# 3PCurrentTX.net
KiCad netlist of a schematic drawn in EAGLE
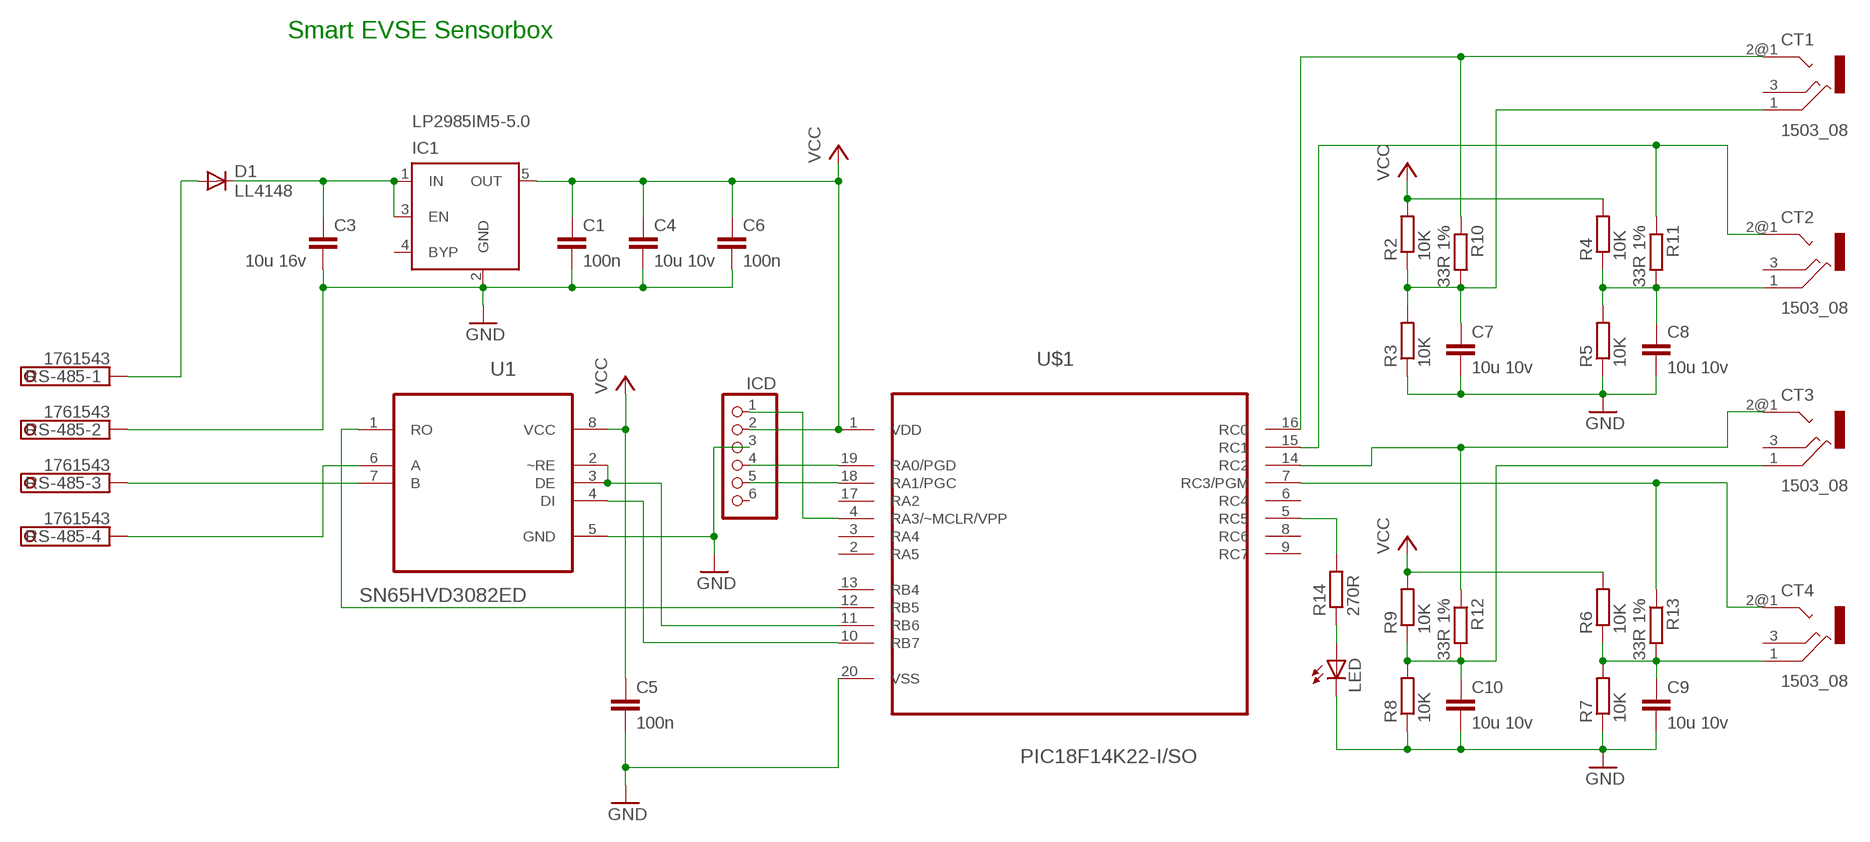
[diagram p0: schematic, sheet 1]

(export (version "E")
  (design (tool "Eeschema 10.0.6"))
  (components
    (comp (ref "C1")
      (value "100n")
      (footprint "eagle-import:C0805K")
      (libsource (lib "eagle-import") (part "C-EUC0805K"))
    )
    (comp (ref "C3")
      (value "10u 16v")
      (footprint "eagle-import:C1206K")
      (libsource (lib "eagle-import") (part "C-EUC1206K"))
    )
    (comp (ref "C4")
      (value "10u 10v")
      (footprint "eagle-import:C0805K")
      (libsource (lib "eagle-import") (part "C-EUC0805K"))
    )
    (comp (ref "C5")
      (value "100n")
      (footprint "eagle-import:C0805K")
      (libsource (lib "eagle-import") (part "C-EUC0805K"))
    )
    (comp (ref "C6")
      (value "100n")
      (footprint "eagle-import:C0805K")
      (libsource (lib "eagle-import") (part "C-EUC0805K"))
    )
    (comp (ref "C7")
      (value "10u 10v")
      (footprint "eagle-import:C0805K")
      (libsource (lib "eagle-import") (part "C-EUC0805K"))
    )
    (comp (ref "C8")
      (value "10u 10v")
      (footprint "eagle-import:C0805K")
      (libsource (lib "eagle-import") (part "C-EUC0805K"))
    )
    (comp (ref "C9")
      (value "10u 10v")
      (footprint "eagle-import:C0805K")
      (libsource (lib "eagle-import") (part "C-EUC0805K"))
    )
    (comp (ref "C10")
      (value "10u 10v")
      (footprint "eagle-import:C0805K")
      (libsource (lib "eagle-import") (part "C-EUC0805K"))
    )
    (comp (ref "CT1")
      (value "1503_08")
      (footprint "eagle-import:1503_08")
      (libsource (lib "eagle-import") (part "1503_?08"))
    )
    (comp (ref "CT2")
      (value "1503_08")
      (footprint "eagle-import:1503_08")
      (libsource (lib "eagle-import") (part "1503_?08"))
    )
    (comp (ref "CT3")
      (value "1503_08")
      (footprint "eagle-import:1503_08")
      (libsource (lib "eagle-import") (part "1503_?08"))
    )
    (comp (ref "CT4")
      (value "1503_08")
      (footprint "eagle-import:1503_08")
      (libsource (lib "eagle-import") (part "1503_?08"))
    )
    (comp (ref "D1")
      (value "LL4148")
      (footprint "eagle-import:SOD123")
      (libsource (lib "eagle-import") (part "DIODE-SOD123"))
    )
    (comp (ref "IC1")
      (value "LP2985IM5-5.0")
      (footprint "eagle-import:SOT23-5")
      (libsource (lib "eagle-import") (part "MIC5219XX"))
    )
    (comp (ref "ICD")
      (value "PINHD-1X6")
      (footprint "eagle-import:1X06")
      (libsource (lib "eagle-import") (part "PINHD-1X6"))
    )
    (comp (ref "LED")
      (value "LEDSML0805")
      (footprint "eagle-import:SML0805")
      (libsource (lib "eagle-import") (part "LEDSML0805"))
    )
    (comp (ref "R2")
      (value "10K")
      (footprint "eagle-import:R0805")
      (libsource (lib "eagle-import") (part "R-EU_R0805"))
    )
    (comp (ref "R3")
      (value "10K")
      (footprint "eagle-import:R0805")
      (libsource (lib "eagle-import") (part "R-EU_R0805"))
    )
    (comp (ref "R4")
      (value "10K")
      (footprint "eagle-import:R0805")
      (libsource (lib "eagle-import") (part "R-EU_R0805"))
    )
    (comp (ref "R5")
      (value "10K")
      (footprint "eagle-import:R0805")
      (libsource (lib "eagle-import") (part "R-EU_R0805"))
    )
    (comp (ref "R6")
      (value "10K")
      (footprint "eagle-import:R0805")
      (libsource (lib "eagle-import") (part "R-EU_R0805"))
    )
    (comp (ref "R7")
      (value "10K")
      (footprint "eagle-import:R0805")
      (libsource (lib "eagle-import") (part "R-EU_R0805"))
    )
    (comp (ref "R8")
      (value "10K")
      (footprint "eagle-import:R0805")
      (libsource (lib "eagle-import") (part "R-EU_R0805"))
    )
    (comp (ref "R9")
      (value "10K")
      (footprint "eagle-import:R0805")
      (libsource (lib "eagle-import") (part "R-EU_R0805"))
    )
    (comp (ref "R10")
      (value "33R 1%")
      (footprint "eagle-import:R0805")
      (libsource (lib "eagle-import") (part "R-EU_R0805"))
    )
    (comp (ref "R11")
      (value "33R 1%")
      (footprint "eagle-import:R0805")
      (libsource (lib "eagle-import") (part "R-EU_R0805"))
    )
    (comp (ref "R12")
      (value "33R 1%")
      (footprint "eagle-import:R0805")
      (libsource (lib "eagle-import") (part "R-EU_R0805"))
    )
    (comp (ref "R13")
      (value "33R 1%")
      (footprint "eagle-import:R0805")
      (libsource (lib "eagle-import") (part "R-EU_R0805"))
    )
    (comp (ref "R14")
      (value "270R")
      (footprint "eagle-import:R0805")
      (libsource (lib "eagle-import") (part "R-EU_R0805"))
    )
    (comp (ref "RS-485")
      (value "1761543")
      (footprint "eagle-import:1751264")
      (fields (field (name "MPN") "1751264"))
      (libsource (lib "eagle-import") (part "1751264"))
    )
    (comp (ref "U$1")
      (value "PIC18F14K22-I/SO")
      (footprint "eagle-import:SOIC127P1030X265-20N")
      (fields (field (name "MPN") "PIC18F14k22-I/SO") (field (name "MPN_1") "PIC18F14k22-I/SO"))
      (libsource (lib "eagle-import") (part "PIC18F14K22-I/SO"))
    )
    (comp (ref "U1")
      (value "SN65HVD3082ED")
      (footprint "eagle-import:SOIC127P600X175-8N")
      (fields (field (name "MPN") "MAX487ECSA+"))
      (libsource (lib "eagle-import") (part "MAX487ECSA+"))
    )
  )
  (nets
    (net (code "1") (name "GND") (class "Default")
      (node (ref "C1") (pin "2") (pinfunction "2_2") (pintype "passive"))
      (node (ref "C10") (pin "2") (pinfunction "2_2") (pintype "passive"))
      (node (ref "C3") (pin "2") (pinfunction "2_2") (pintype "passive"))
      (node (ref "C4") (pin "2") (pinfunction "2_2") (pintype "passive"))
      (node (ref "C5") (pin "2") (pinfunction "2_2") (pintype "passive"))
      (node (ref "C6") (pin "2") (pinfunction "2_2") (pintype "passive"))
      (node (ref "C7") (pin "2") (pinfunction "2_2") (pintype "passive"))
      (node (ref "C8") (pin "2") (pinfunction "2_2") (pintype "passive"))
      (node (ref "C9") (pin "2") (pinfunction "2_2") (pintype "passive"))
      (node (ref "IC1") (pin "2") (pinfunction "GND_2") (pintype "power_in"))
      (node (ref "ICD") (pin "3") (pinfunction "3_3") (pintype "passive"))
      (node (ref "LED") (pin "C") (pinfunction "C_C") (pintype "passive"))
      (node (ref "R3") (pin "1") (pinfunction "1_1") (pintype "passive"))
      (node (ref "R5") (pin "1") (pinfunction "1_1") (pintype "passive"))
      (node (ref "R7") (pin "1") (pinfunction "1_1") (pintype "passive"))
      (node (ref "R8") (pin "1") (pinfunction "1_1") (pintype "passive"))
      (node (ref "RS-485") (pin "2") (pinfunction "K_2") (pintype "passive"))
      (node (ref "U$1") (pin "20") (pinfunction "VSS_20") (pintype "passive"))
      (node (ref "U1") (pin "5") (pinfunction "GND_5") (pintype "passive"))
    )
    (net (code "2") (name "Net-(C7-Pad1)") (class "Default")
      (node (ref "C7") (pin "1") (pinfunction "1_1") (pintype "passive"))
      (node (ref "CT1") (pin "1") (pinfunction "1_1") (pintype "passive"))
      (node (ref "R10") (pin "2") (pinfunction "2_2") (pintype "passive"))
      (node (ref "R2") (pin "1") (pinfunction "1_1") (pintype "passive"))
      (node (ref "R3") (pin "2") (pinfunction "2_2") (pintype "passive"))
    )
    (net (code "3") (name "Net-(C8-Pad1)") (class "Default")
      (node (ref "C8") (pin "1") (pinfunction "1_1") (pintype "passive"))
      (node (ref "CT2") (pin "1") (pinfunction "1_1") (pintype "passive"))
      (node (ref "R11") (pin "2") (pinfunction "2_2") (pintype "passive"))
      (node (ref "R4") (pin "1") (pinfunction "1_1") (pintype "passive"))
      (node (ref "R5") (pin "2") (pinfunction "2_2") (pintype "passive"))
    )
    (net (code "4") (name "Net-(C9-Pad1)") (class "Default")
      (node (ref "C9") (pin "1") (pinfunction "1_1") (pintype "passive"))
      (node (ref "CT4") (pin "1") (pinfunction "1_1") (pintype "passive"))
      (node (ref "R13") (pin "2") (pinfunction "2_2") (pintype "passive"))
      (node (ref "R6") (pin "1") (pinfunction "1_1") (pintype "passive"))
      (node (ref "R7") (pin "2") (pinfunction "2_2") (pintype "passive"))
    )
    (net (code "5") (name "Net-(C10-Pad1)") (class "Default")
      (node (ref "C10") (pin "1") (pinfunction "1_1") (pintype "passive"))
      (node (ref "CT3") (pin "1") (pinfunction "1_1") (pintype "passive"))
      (node (ref "R12") (pin "2") (pinfunction "2_2") (pintype "passive"))
      (node (ref "R8") (pin "2") (pinfunction "2_2") (pintype "passive"))
      (node (ref "R9") (pin "1") (pinfunction "1_1") (pintype "passive"))
    )
    (net (code "6") (name "Net-(IC1-EN)") (class "Default")
      (node (ref "C3") (pin "1") (pinfunction "1_1") (pintype "passive"))
      (node (ref "D1") (pin "C") (pinfunction "C_C") (pintype "passive"))
      (node (ref "IC1") (pin "1") (pinfunction "IN_1") (pintype "input"))
      (node (ref "IC1") (pin "3") (pinfunction "EN_3") (pintype "input"))
    )
    (net (code "7") (name "Net-(LED-PadA)") (class "Default")
      (node (ref "LED") (pin "A") (pinfunction "A_A") (pintype "passive"))
      (node (ref "R14") (pin "1") (pinfunction "1_1") (pintype "passive"))
    )
    (net (code "8") (name "Net-(RS-485A-K)") (class "Default")
      (node (ref "D1") (pin "A") (pinfunction "A_A") (pintype "passive"))
      (node (ref "RS-485") (pin "1") (pinfunction "K_1") (pintype "passive"))
    )
    (net (code "9") (name "Net-(RS-485C-K)") (class "Default")
      (node (ref "RS-485") (pin "3") (pinfunction "K_3") (pintype "passive"))
      (node (ref "U1") (pin "7") (pinfunction "B_7") (pintype "bidirectional"))
    )
    (net (code "10") (name "Net-(RS-485D-K)") (class "Default")
      (node (ref "RS-485") (pin "4") (pinfunction "K_4") (pintype "passive"))
      (node (ref "U1") (pin "6") (pinfunction "A_6") (pintype "bidirectional"))
    )
    (net (code "11") (name "Net-(U$1-RA0{slash}PGD)") (class "Default")
      (node (ref "ICD") (pin "4") (pinfunction "4_4") (pintype "passive"))
      (node (ref "U$1") (pin "19") (pinfunction "RA0/PGD_19") (pintype "bidirectional"))
    )
    (net (code "12") (name "Net-(U$1-RA1{slash}PGC)") (class "Default")
      (node (ref "ICD") (pin "5") (pinfunction "5_5") (pintype "passive"))
      (node (ref "U$1") (pin "18") (pinfunction "RA1/PGC_18") (pintype "bidirectional"))
    )
    (net (code "13") (name "Net-(U$1-RA3{slash}~{MCLR{slash}VPP})") (class "Default")
      (node (ref "ICD") (pin "1") (pinfunction "1_1") (pintype "passive"))
      (node (ref "U$1") (pin "4") (pinfunction "RA3/~{MCLR/VPP}_4") (pintype "bidirectional"))
    )
    (net (code "14") (name "Net-(U$1-RB5)") (class "Default")
      (node (ref "U$1") (pin "12") (pinfunction "RB5_12") (pintype "bidirectional"))
      (node (ref "U1") (pin "1") (pinfunction "RO_1") (pintype "output"))
    )
    (net (code "15") (name "Net-(U$1-RB6)") (class "Default")
      (node (ref "U$1") (pin "11") (pinfunction "RB6_11") (pintype "bidirectional"))
      (node (ref "U1") (pin "2") (pinfunction "~{RE}_2") (pintype "input"))
      (node (ref "U1") (pin "3") (pinfunction "DE_3") (pintype "input"))
    )
    (net (code "16") (name "Net-(U$1-RB7)") (class "Default")
      (node (ref "U$1") (pin "10") (pinfunction "RB7_10") (pintype "bidirectional"))
      (node (ref "U1") (pin "4") (pinfunction "DI_4") (pintype "input"))
    )
    (net (code "17") (name "Net-(U$1-RC0)") (class "Default")
      (node (ref "CT1") (pin "2@1") (pinfunction "2_2@1") (pintype "passive"))
      (node (ref "R10") (pin "1") (pinfunction "1_1") (pintype "passive"))
      (node (ref "U$1") (pin "16") (pinfunction "RC0_16") (pintype "bidirectional"))
    )
    (net (code "18") (name "Net-(U$1-RC1)") (class "Default")
      (node (ref "CT2") (pin "2@1") (pinfunction "2_2@1") (pintype "passive"))
      (node (ref "R11") (pin "1") (pinfunction "1_1") (pintype "passive"))
      (node (ref "U$1") (pin "15") (pinfunction "RC1_15") (pintype "bidirectional"))
    )
    (net (code "19") (name "Net-(U$1-RC2)") (class "Default")
      (node (ref "CT3") (pin "2@1") (pinfunction "2_2@1") (pintype "passive"))
      (node (ref "R12") (pin "1") (pinfunction "1_1") (pintype "passive"))
      (node (ref "U$1") (pin "14") (pinfunction "RC2_14") (pintype "bidirectional"))
    )
    (net (code "20") (name "Net-(U$1-RC3{slash}PGM)") (class "Default")
      (node (ref "CT4") (pin "2@1") (pinfunction "2_2@1") (pintype "passive"))
      (node (ref "R13") (pin "1") (pinfunction "1_1") (pintype "passive"))
      (node (ref "U$1") (pin "7") (pinfunction "RC3/PGM_7") (pintype "bidirectional"))
    )
    (net (code "21") (name "Net-(U$1-RC5)") (class "Default")
      (node (ref "R14") (pin "2") (pinfunction "2_2") (pintype "passive"))
      (node (ref "U$1") (pin "5") (pinfunction "RC5_5") (pintype "bidirectional"))
    )
    (net (code "22") (name "VCC") (class "Default")
      (node (ref "C1") (pin "1") (pinfunction "1_1") (pintype "passive"))
      (node (ref "C4") (pin "1") (pinfunction "1_1") (pintype "passive"))
      (node (ref "C5") (pin "1") (pinfunction "1_1") (pintype "passive"))
      (node (ref "C6") (pin "1") (pinfunction "1_1") (pintype "passive"))
      (node (ref "IC1") (pin "5") (pinfunction "OUT_5") (pintype "output"))
      (node (ref "ICD") (pin "2") (pinfunction "2_2") (pintype "passive"))
      (node (ref "R2") (pin "2") (pinfunction "2_2") (pintype "passive"))
      (node (ref "R4") (pin "2") (pinfunction "2_2") (pintype "passive"))
      (node (ref "R6") (pin "2") (pinfunction "2_2") (pintype "passive"))
      (node (ref "R9") (pin "2") (pinfunction "2_2") (pintype "passive"))
      (node (ref "U$1") (pin "1") (pinfunction "VDD_1") (pintype "power_in"))
      (node (ref "U1") (pin "8") (pinfunction "VCC_8") (pintype "power_in"))
    )
    (net (code "23") (name "unconnected-(CT1-2-Pad2@2)") (class "Default")
      (node (ref "CT1") (pin "2@2") (pinfunction "2_2@2") (pintype "passive"))
    )
    (net (code "24") (name "unconnected-(CT1-Pad3)") (class "Default")
      (node (ref "CT1") (pin "3") (pinfunction "3_3") (pintype "passive"))
    )
    (net (code "25") (name "unconnected-(CT2-2-Pad2@2)") (class "Default")
      (node (ref "CT2") (pin "2@2") (pinfunction "2_2@2") (pintype "passive"))
    )
    (net (code "26") (name "unconnected-(CT2-Pad3)") (class "Default")
      (node (ref "CT2") (pin "3") (pinfunction "3_3") (pintype "passive"))
    )
    (net (code "27") (name "unconnected-(CT3-2-Pad2@2)") (class "Default")
      (node (ref "CT3") (pin "2@2") (pinfunction "2_2@2") (pintype "passive"))
    )
    (net (code "28") (name "unconnected-(CT3-Pad3)") (class "Default")
      (node (ref "CT3") (pin "3") (pinfunction "3_3") (pintype "passive"))
    )
    (net (code "29") (name "unconnected-(CT4-2-Pad2@2)") (class "Default")
      (node (ref "CT4") (pin "2@2") (pinfunction "2_2@2") (pintype "passive"))
    )
    (net (code "30") (name "unconnected-(CT4-Pad3)") (class "Default")
      (node (ref "CT4") (pin "3") (pinfunction "3_3") (pintype "passive"))
    )
    (net (code "31") (name "unconnected-(IC1-BYP-Pad4)") (class "Default")
      (node (ref "IC1") (pin "4") (pinfunction "BYP_4") (pintype "passive"))
    )
    (net (code "32") (name "unconnected-(ICD-Pad6)") (class "Default")
      (node (ref "ICD") (pin "6") (pinfunction "6_6") (pintype "passive"))
    )
    (net (code "33") (name "unconnected-(U$1-RA2-Pad17)") (class "Default")
      (node (ref "U$1") (pin "17") (pinfunction "RA2_17") (pintype "bidirectional"))
    )
    (net (code "34") (name "unconnected-(U$1-RA4-Pad3)") (class "Default")
      (node (ref "U$1") (pin "3") (pinfunction "RA4_3") (pintype "bidirectional"))
    )
    (net (code "35") (name "unconnected-(U$1-RA5-Pad2)") (class "Default")
      (node (ref "U$1") (pin "2") (pinfunction "RA5_2") (pintype "bidirectional"))
    )
    (net (code "36") (name "unconnected-(U$1-RB4-Pad13)") (class "Default")
      (node (ref "U$1") (pin "13") (pinfunction "RB4_13") (pintype "bidirectional"))
    )
    (net (code "37") (name "unconnected-(U$1-RC4-Pad6)") (class "Default")
      (node (ref "U$1") (pin "6") (pinfunction "RC4_6") (pintype "bidirectional"))
    )
    (net (code "38") (name "unconnected-(U$1-RC6-Pad8)") (class "Default")
      (node (ref "U$1") (pin "8") (pinfunction "RC6_8") (pintype "bidirectional"))
    )
    (net (code "39") (name "unconnected-(U$1-RC7-Pad9)") (class "Default")
      (node (ref "U$1") (pin "9") (pinfunction "RC7_9") (pintype "bidirectional"))
    )
  )
)
